# hbridge.net
KiCad netlist of a schematic drawn in EAGLE
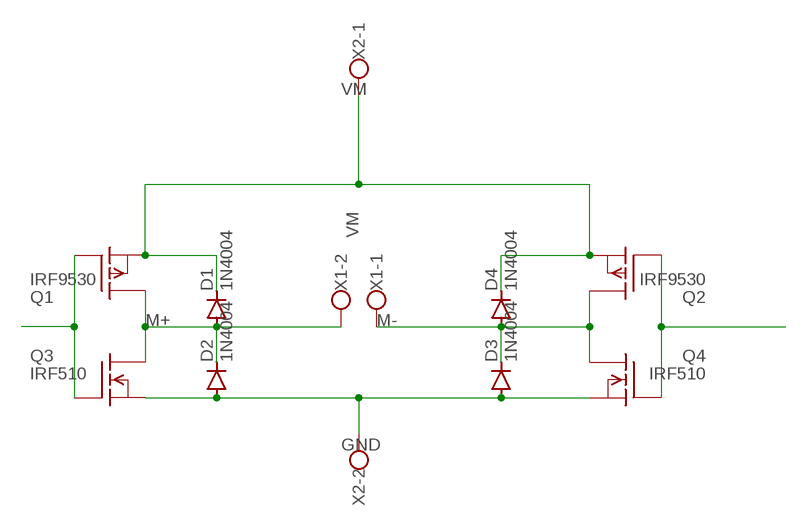
[diagram p0: schematic, sheet 1]

(export (version "E")
  (design (tool "Eeschema 10.0.6"))
  (components
    (comp (ref "D1")
      (value "1N4004")
      (footprint "eagle-import:DO41-10")
      (libsource (lib "eagle-import") (part "1N4004"))
    )
    (comp (ref "D2")
      (value "1N4004")
      (footprint "eagle-import:DO41-10")
      (libsource (lib "eagle-import") (part "1N4004"))
    )
    (comp (ref "D3")
      (value "1N4004")
      (footprint "eagle-import:DO41-10")
      (libsource (lib "eagle-import") (part "1N4004"))
    )
    (comp (ref "D4")
      (value "1N4004")
      (footprint "eagle-import:DO41-10")
      (libsource (lib "eagle-import") (part "1N4004"))
    )
    (comp (ref "Q1")
      (value "IRF9530")
      (footprint "eagle-import:TO220")
      (libsource (lib "eagle-import") (part "IRF9530"))
    )
    (comp (ref "Q2")
      (value "IRF9530")
      (footprint "eagle-import:TO220")
      (libsource (lib "eagle-import") (part "IRF9530"))
    )
    (comp (ref "Q3")
      (value "IRF510")
      (footprint "eagle-import:TO220")
      (libsource (lib "eagle-import") (part "IRF510"))
    )
    (comp (ref "Q4")
      (value "IRF510")
      (footprint "eagle-import:TO220")
      (libsource (lib "eagle-import") (part "IRF510"))
    )
    (comp (ref "X1")
      (value "W237-102")
      (footprint "eagle-import:W237-102")
      (fields (field (name "MPN") "237-102"))
      (libsource (lib "eagle-import") (part "W237-102"))
    )
    (comp (ref "X2")
      (value "W237-102")
      (footprint "eagle-import:W237-102")
      (fields (field (name "MPN") "237-102"))
      (libsource (lib "eagle-import") (part "W237-102"))
    )
  )
  (nets
    (net (code "1") (name "/GND") (class "Default")
      (node (ref "D2") (pin "A") (pinfunction "A_A") (pintype "passive"))
      (node (ref "D3") (pin "A") (pinfunction "A_A") (pintype "passive"))
      (node (ref "Q3") (pin "3") (pinfunction "S_3") (pintype "passive"))
      (node (ref "Q4") (pin "3") (pinfunction "S_3") (pintype "passive"))
      (node (ref "X2") (pin "2") (pinfunction "KL_2") (pintype "passive"))
    )
    (net (code "2") (name "/M+") (class "Default")
      (node (ref "D1") (pin "A") (pinfunction "A_A") (pintype "passive"))
      (node (ref "D2") (pin "C") (pinfunction "C_C") (pintype "passive"))
      (node (ref "Q1") (pin "2") (pinfunction "D_2") (pintype "passive"))
      (node (ref "Q3") (pin "2") (pinfunction "D_2") (pintype "passive"))
      (node (ref "X1") (pin "2") (pinfunction "KL_2") (pintype "passive"))
    )
    (net (code "3") (name "/M-") (class "Default")
      (node (ref "D3") (pin "C") (pinfunction "C_C") (pintype "passive"))
      (node (ref "D4") (pin "A") (pinfunction "A_A") (pintype "passive"))
      (node (ref "Q2") (pin "2") (pinfunction "D_2") (pintype "passive"))
      (node (ref "Q4") (pin "2") (pinfunction "D_2") (pintype "passive"))
      (node (ref "X1") (pin "1") (pinfunction "KL_1") (pintype "passive"))
    )
    (net (code "4") (name "/VM") (class "Default")
      (node (ref "D1") (pin "C") (pinfunction "C_C") (pintype "passive"))
      (node (ref "D4") (pin "C") (pinfunction "C_C") (pintype "passive"))
      (node (ref "Q1") (pin "3") (pinfunction "S_3") (pintype "passive"))
      (node (ref "Q2") (pin "3") (pinfunction "S_3") (pintype "passive"))
      (node (ref "X2") (pin "1") (pinfunction "KL_1") (pintype "passive"))
    )
    (net (code "5") (name "Net-(Q1-G)") (class "Default")
      (node (ref "Q1") (pin "1") (pinfunction "G_1") (pintype "passive"))
      (node (ref "Q3") (pin "1") (pinfunction "G_1") (pintype "passive"))
    )
    (net (code "6") (name "Net-(Q2-G)") (class "Default")
      (node (ref "Q2") (pin "1") (pinfunction "G_1") (pintype "passive"))
      (node (ref "Q4") (pin "1") (pinfunction "G_1") (pintype "passive"))
    )
  )
)
